# sch_smd_1206_component_only_component2.net
KiCad netlist of a schematic drawn in EAGLE
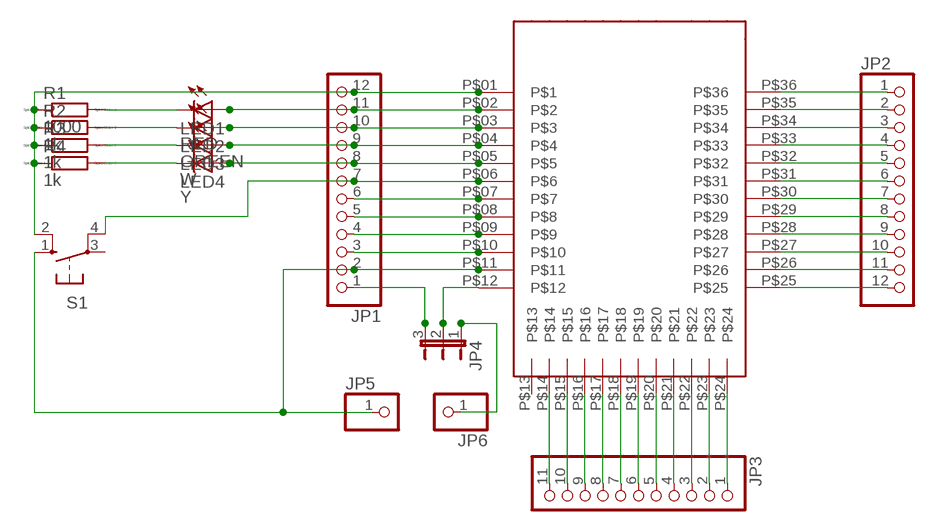
[diagram p0: schematic, sheet 1]

(export (version "E")
  (design (tool "Eeschema 10.0.6"))
  (components
    (comp (ref "JP1")
      (value "PINHD-1X12")
      (footprint "eagle-import:1X12")
      (fields (field (name "SPICEPREFIX") "X"))
      (libsource (lib "eagle-import") (part "PINHD-1X12"))
    )
    (comp (ref "JP2")
      (value "PINHD-1X12")
      (footprint "eagle-import:1X12")
      (libsource (lib "eagle-import") (part "PINHD-1X12"))
    )
    (comp (ref "JP3")
      (value "PINHD-1X11")
      (footprint "eagle-import:1X11")
      (libsource (lib "eagle-import") (part "PINHD-1X11"))
    )
    (comp (ref "JP4")
      (value "JP2E")
      (footprint "eagle-import:JP2")
      (libsource (lib "eagle-import") (part "JP2E"))
    )
    (comp (ref "JP5")
      (value "PINHD-1X1")
      (footprint "eagle-import:1X01")
      (libsource (lib "eagle-import") (part "PINHD-1X1"))
    )
    (comp (ref "JP6")
      (value "PINHD-1X1")
      (footprint "eagle-import:1X01")
      (libsource (lib "eagle-import") (part "PINHD-1X1"))
    )
    (comp (ref "LED1")
      (value "RED")
      (footprint "eagle-import:LED3MM")
      (libsource (lib "eagle-import") (part "LED3MM"))
    )
    (comp (ref "LED2")
      (value "GREEN")
      (footprint "eagle-import:LED3MM")
      (libsource (lib "eagle-import") (part "LED3MM"))
    )
    (comp (ref "LED3")
      (value "W")
      (footprint "eagle-import:LED3MM")
      (libsource (lib "eagle-import") (part "LED3MM"))
    )
    (comp (ref "LED4")
      (value "Y")
      (footprint "eagle-import:LED3MM")
      (libsource (lib "eagle-import") (part "LED3MM"))
    )
    (comp (ref "R1")
      (value "1000")
      (footprint "eagle-import:0204_7")
      (libsource (lib "eagle-import") (part "R0204/7"))
    )
    (comp (ref "R2")
      (value "1k")
      (footprint "eagle-import:0204_7")
      (libsource (lib "eagle-import") (part "R0204/7"))
    )
    (comp (ref "R3")
      (value "1k")
      (footprint "eagle-import:0204_7")
      (libsource (lib "eagle-import") (part "R0204/7"))
    )
    (comp (ref "R4")
      (value "1k")
      (footprint "eagle-import:0204_7")
      (libsource (lib "eagle-import") (part "R0204/7"))
    )
    (comp (ref "S1")
      (value "10-XX")
      (footprint "eagle-import:B3F-10XX")
      (fields (field (name "MPN") "B3F-1000"))
      (libsource (lib "eagle-import") (part "10-XX"))
    )
    (comp (ref "U$1")
      (value "HZX_MODULE")
      (footprint "eagle-import:SMD_PAD_VERSION")
      (fields (field (name "AUTHOR") "Agam"))
      (libsource (lib "eagle-import") (part "HZX_MODULE"))
    )
  )
  (nets
    (net (code "1") (name "Net-(JP1-Pad1)") (class "Default")
      (node (ref "JP1") (pin "1") (pinfunction "1_1") (pintype "passive"))
      (node (ref "JP4") (pin "3") (pinfunction "3_3") (pintype "passive"))
    )
    (net (code "2") (name "Net-(JP1-Pad3)") (class "Default")
      (node (ref "JP1") (pin "3") (pinfunction "3_3") (pintype "passive"))
      (node (ref "U$1") (pin "P$10") (pinfunction "P$10_P$10") (pintype "bidirectional"))
    )
    (net (code "3") (name "Net-(JP2-Pad1)") (class "Default")
      (node (ref "JP2") (pin "1") (pinfunction "1_1") (pintype "passive"))
      (node (ref "U$1") (pin "P$36") (pinfunction "P$36_P$36") (pintype "bidirectional"))
    )
    (net (code "4") (name "Net-(JP2-Pad2)") (class "Default")
      (node (ref "JP2") (pin "2") (pinfunction "2_2") (pintype "passive"))
      (node (ref "U$1") (pin "P$35") (pinfunction "P$35_P$35") (pintype "bidirectional"))
    )
    (net (code "5") (name "Net-(JP2-Pad3)") (class "Default")
      (node (ref "JP2") (pin "3") (pinfunction "3_3") (pintype "passive"))
      (node (ref "U$1") (pin "P$34") (pinfunction "P$34_P$34") (pintype "bidirectional"))
    )
    (net (code "6") (name "Net-(JP2-Pad4)") (class "Default")
      (node (ref "JP2") (pin "4") (pinfunction "4_4") (pintype "passive"))
      (node (ref "U$1") (pin "P$33") (pinfunction "P$33_P$33") (pintype "bidirectional"))
    )
    (net (code "7") (name "Net-(JP2-Pad5)") (class "Default")
      (node (ref "JP2") (pin "5") (pinfunction "5_5") (pintype "passive"))
      (node (ref "U$1") (pin "P$32") (pinfunction "P$32_P$32") (pintype "bidirectional"))
    )
    (net (code "8") (name "Net-(JP2-Pad6)") (class "Default")
      (node (ref "JP2") (pin "6") (pinfunction "6_6") (pintype "passive"))
      (node (ref "U$1") (pin "P$31") (pinfunction "P$31_P$31") (pintype "bidirectional"))
    )
    (net (code "9") (name "Net-(JP2-Pad7)") (class "Default")
      (node (ref "JP2") (pin "7") (pinfunction "7_7") (pintype "passive"))
      (node (ref "U$1") (pin "P$30") (pinfunction "P$30_P$30") (pintype "bidirectional"))
    )
    (net (code "10") (name "Net-(JP2-Pad8)") (class "Default")
      (node (ref "JP2") (pin "8") (pinfunction "8_8") (pintype "passive"))
      (node (ref "U$1") (pin "P$29") (pinfunction "P$29_P$29") (pintype "bidirectional"))
    )
    (net (code "11") (name "Net-(JP2-Pad9)") (class "Default")
      (node (ref "JP2") (pin "9") (pinfunction "9_9") (pintype "passive"))
      (node (ref "U$1") (pin "P$28") (pinfunction "P$28_P$28") (pintype "bidirectional"))
    )
    (net (code "12") (name "Net-(JP2-Pad10)") (class "Default")
      (node (ref "JP2") (pin "10") (pinfunction "10_10") (pintype "passive"))
      (node (ref "U$1") (pin "P$27") (pinfunction "P$27_P$27") (pintype "bidirectional"))
    )
    (net (code "13") (name "Net-(JP2-Pad11)") (class "Default")
      (node (ref "JP2") (pin "11") (pinfunction "11_11") (pintype "passive"))
      (node (ref "U$1") (pin "P$26") (pinfunction "P$26_P$26") (pintype "bidirectional"))
    )
    (net (code "14") (name "Net-(JP2-Pad12)") (class "Default")
      (node (ref "JP2") (pin "12") (pinfunction "12_12") (pintype "passive"))
      (node (ref "U$1") (pin "P$25") (pinfunction "P$25_P$25") (pintype "bidirectional"))
    )
    (net (code "15") (name "Net-(JP3-Pad1)") (class "Default")
      (node (ref "JP3") (pin "1") (pinfunction "1_1") (pintype "passive"))
      (node (ref "U$1") (pin "P$24") (pinfunction "P$24_P$24") (pintype "bidirectional"))
    )
    (net (code "16") (name "Net-(JP3-Pad2)") (class "Default")
      (node (ref "JP3") (pin "2") (pinfunction "2_2") (pintype "passive"))
      (node (ref "U$1") (pin "P$23") (pinfunction "P$23_P$23") (pintype "bidirectional"))
    )
    (net (code "17") (name "Net-(JP3-Pad3)") (class "Default")
      (node (ref "JP3") (pin "3") (pinfunction "3_3") (pintype "passive"))
      (node (ref "U$1") (pin "P$22") (pinfunction "P$22_P$22") (pintype "bidirectional"))
    )
    (net (code "18") (name "Net-(JP3-Pad4)") (class "Default")
      (node (ref "JP3") (pin "4") (pinfunction "4_4") (pintype "passive"))
      (node (ref "U$1") (pin "P$21") (pinfunction "P$21_P$21") (pintype "bidirectional"))
    )
    (net (code "19") (name "Net-(JP3-Pad5)") (class "Default")
      (node (ref "JP3") (pin "5") (pinfunction "5_5") (pintype "passive"))
      (node (ref "U$1") (pin "P$20") (pinfunction "P$20_P$20") (pintype "bidirectional"))
    )
    (net (code "20") (name "Net-(JP3-Pad6)") (class "Default")
      (node (ref "JP3") (pin "6") (pinfunction "6_6") (pintype "passive"))
      (node (ref "U$1") (pin "P$19") (pinfunction "P$19_P$19") (pintype "bidirectional"))
    )
    (net (code "21") (name "Net-(JP3-Pad7)") (class "Default")
      (node (ref "JP3") (pin "7") (pinfunction "7_7") (pintype "passive"))
      (node (ref "U$1") (pin "P$18") (pinfunction "P$18_P$18") (pintype "bidirectional"))
    )
    (net (code "22") (name "Net-(JP3-Pad8)") (class "Default")
      (node (ref "JP3") (pin "8") (pinfunction "8_8") (pintype "passive"))
      (node (ref "U$1") (pin "P$17") (pinfunction "P$17_P$17") (pintype "bidirectional"))
    )
    (net (code "23") (name "Net-(JP3-Pad9)") (class "Default")
      (node (ref "JP3") (pin "9") (pinfunction "9_9") (pintype "passive"))
      (node (ref "U$1") (pin "P$16") (pinfunction "P$16_P$16") (pintype "bidirectional"))
    )
    (net (code "24") (name "Net-(JP3-Pad10)") (class "Default")
      (node (ref "JP3") (pin "10") (pinfunction "10_10") (pintype "passive"))
      (node (ref "U$1") (pin "P$15") (pinfunction "P$15_P$15") (pintype "bidirectional"))
    )
    (net (code "25") (name "Net-(JP3-Pad11)") (class "Default")
      (node (ref "JP3") (pin "11") (pinfunction "11_11") (pintype "passive"))
      (node (ref "U$1") (pin "P$14") (pinfunction "P$14_P$14") (pintype "bidirectional"))
    )
    (net (code "26") (name "Net-(JP4-Pad1)") (class "Default")
      (node (ref "JP4") (pin "1") (pinfunction "1_1") (pintype "passive"))
      (node (ref "JP6") (pin "1") (pinfunction "1_1") (pintype "passive"))
    )
    (net (code "27") (name "Net-(JP4-Pad2)") (class "Default")
      (node (ref "JP4") (pin "2") (pinfunction "2_2") (pintype "passive"))
      (node (ref "U$1") (pin "P$12") (pinfunction "P$12_P$12") (pintype "bidirectional"))
    )
    (net (code "28") (name "Net-(LED1-C)") (class "Default")
      (node (ref "LED1") (pin "K") (pinfunction "C_K") (pintype "passive"))
      (node (ref "R1") (pin "2") (pinfunction "2_2") (pintype "passive"))
    )
    (net (code "29") (name "Net-(LED2-C)") (class "Default")
      (node (ref "LED2") (pin "K") (pinfunction "C_K") (pintype "passive"))
      (node (ref "R2") (pin "2") (pinfunction "2_2") (pintype "passive"))
    )
    (net (code "30") (name "Net-(LED3-C)") (class "Default")
      (node (ref "LED3") (pin "K") (pinfunction "C_K") (pintype "passive"))
      (node (ref "R3") (pin "2") (pinfunction "2_2") (pintype "passive"))
    )
    (net (code "31") (name "Net-(LED4-C)") (class "Default")
      (node (ref "LED4") (pin "K") (pinfunction "C_K") (pintype "passive"))
      (node (ref "R4") (pin "2") (pinfunction "2_2") (pintype "passive"))
    )
    (net (code "32") (name "Net-(S1-P1)") (class "Default")
      (node (ref "JP1") (pin "7") (pinfunction "7_7") (pintype "passive"))
      (node (ref "S1") (pin "4") (pinfunction "P1_4") (pintype "passive"))
      (node (ref "U$1") (pin "P$06") (pinfunction "P$6_P$06") (pintype "bidirectional"))
    )
    (net (code "33") (name "Net-(S1-S)") (class "Default")
      (node (ref "JP1") (pin "2") (pinfunction "2_2") (pintype "passive"))
      (node (ref "JP5") (pin "1") (pinfunction "1_1") (pintype "passive"))
      (node (ref "S1") (pin "1") (pinfunction "S_1") (pintype "passive"))
      (node (ref "U$1") (pin "P$11") (pinfunction "P$11_P$11") (pintype "bidirectional"))
    )
    (net (code "34") (name "Net-(S1-S1)") (class "Default")
      (node (ref "JP1") (pin "12") (pinfunction "12_12") (pintype "passive"))
      (node (ref "R1") (pin "1") (pinfunction "1_1") (pintype "passive"))
      (node (ref "R2") (pin "1") (pinfunction "1_1") (pintype "passive"))
      (node (ref "R3") (pin "1") (pinfunction "1_1") (pintype "passive"))
      (node (ref "R4") (pin "1") (pinfunction "1_1") (pintype "passive"))
      (node (ref "S1") (pin "2") (pinfunction "S1_2") (pintype "passive"))
      (node (ref "U$1") (pin "P$01") (pinfunction "P$1_P$01") (pintype "bidirectional"))
    )
    (net (code "35") (name "Net-(U$1-P$2)") (class "Default")
      (node (ref "JP1") (pin "11") (pinfunction "11_11") (pintype "passive"))
      (node (ref "LED1") (pin "A") (pinfunction "A_A") (pintype "passive"))
      (node (ref "U$1") (pin "P$02") (pinfunction "P$2_P$02") (pintype "bidirectional"))
    )
    (net (code "36") (name "Net-(U$1-P$3)") (class "Default")
      (node (ref "JP1") (pin "10") (pinfunction "10_10") (pintype "passive"))
      (node (ref "LED2") (pin "A") (pinfunction "A_A") (pintype "passive"))
      (node (ref "U$1") (pin "P$03") (pinfunction "P$3_P$03") (pintype "bidirectional"))
    )
    (net (code "37") (name "Net-(U$1-P$4)") (class "Default")
      (node (ref "JP1") (pin "9") (pinfunction "9_9") (pintype "passive"))
      (node (ref "LED3") (pin "A") (pinfunction "A_A") (pintype "passive"))
      (node (ref "U$1") (pin "P$04") (pinfunction "P$4_P$04") (pintype "bidirectional"))
    )
    (net (code "38") (name "Net-(U$1-P$5)") (class "Default")
      (node (ref "JP1") (pin "8") (pinfunction "8_8") (pintype "passive"))
      (node (ref "LED4") (pin "A") (pinfunction "A_A") (pintype "passive"))
      (node (ref "U$1") (pin "P$05") (pinfunction "P$5_P$05") (pintype "bidirectional"))
    )
    (net (code "39") (name "Net-(U$1-P$7)") (class "Default")
      (node (ref "JP1") (pin "6") (pinfunction "6_6") (pintype "passive"))
      (node (ref "U$1") (pin "P$07") (pinfunction "P$7_P$07") (pintype "bidirectional"))
    )
    (net (code "40") (name "Net-(U$1-P$8)") (class "Default")
      (node (ref "JP1") (pin "5") (pinfunction "5_5") (pintype "passive"))
      (node (ref "U$1") (pin "P$08") (pinfunction "P$8_P$08") (pintype "bidirectional"))
    )
    (net (code "41") (name "Net-(U$1-P$9)") (class "Default")
      (node (ref "JP1") (pin "4") (pinfunction "4_4") (pintype "passive"))
      (node (ref "U$1") (pin "P$09") (pinfunction "P$9_P$09") (pintype "bidirectional"))
    )
    (net (code "42") (name "unconnected-(S1-P-Pad3)") (class "Default")
      (node (ref "S1") (pin "3") (pinfunction "P_3") (pintype "passive"))
    )
    (net (code "43") (name "unconnected-(U$1-PadP$13)") (class "Default")
      (node (ref "U$1") (pin "P$13") (pinfunction "P$13_P$13") (pintype "bidirectional"))
    )
  )
)
